# AC_Detection.net
KiCad netlist of a schematic drawn in Altium Designer
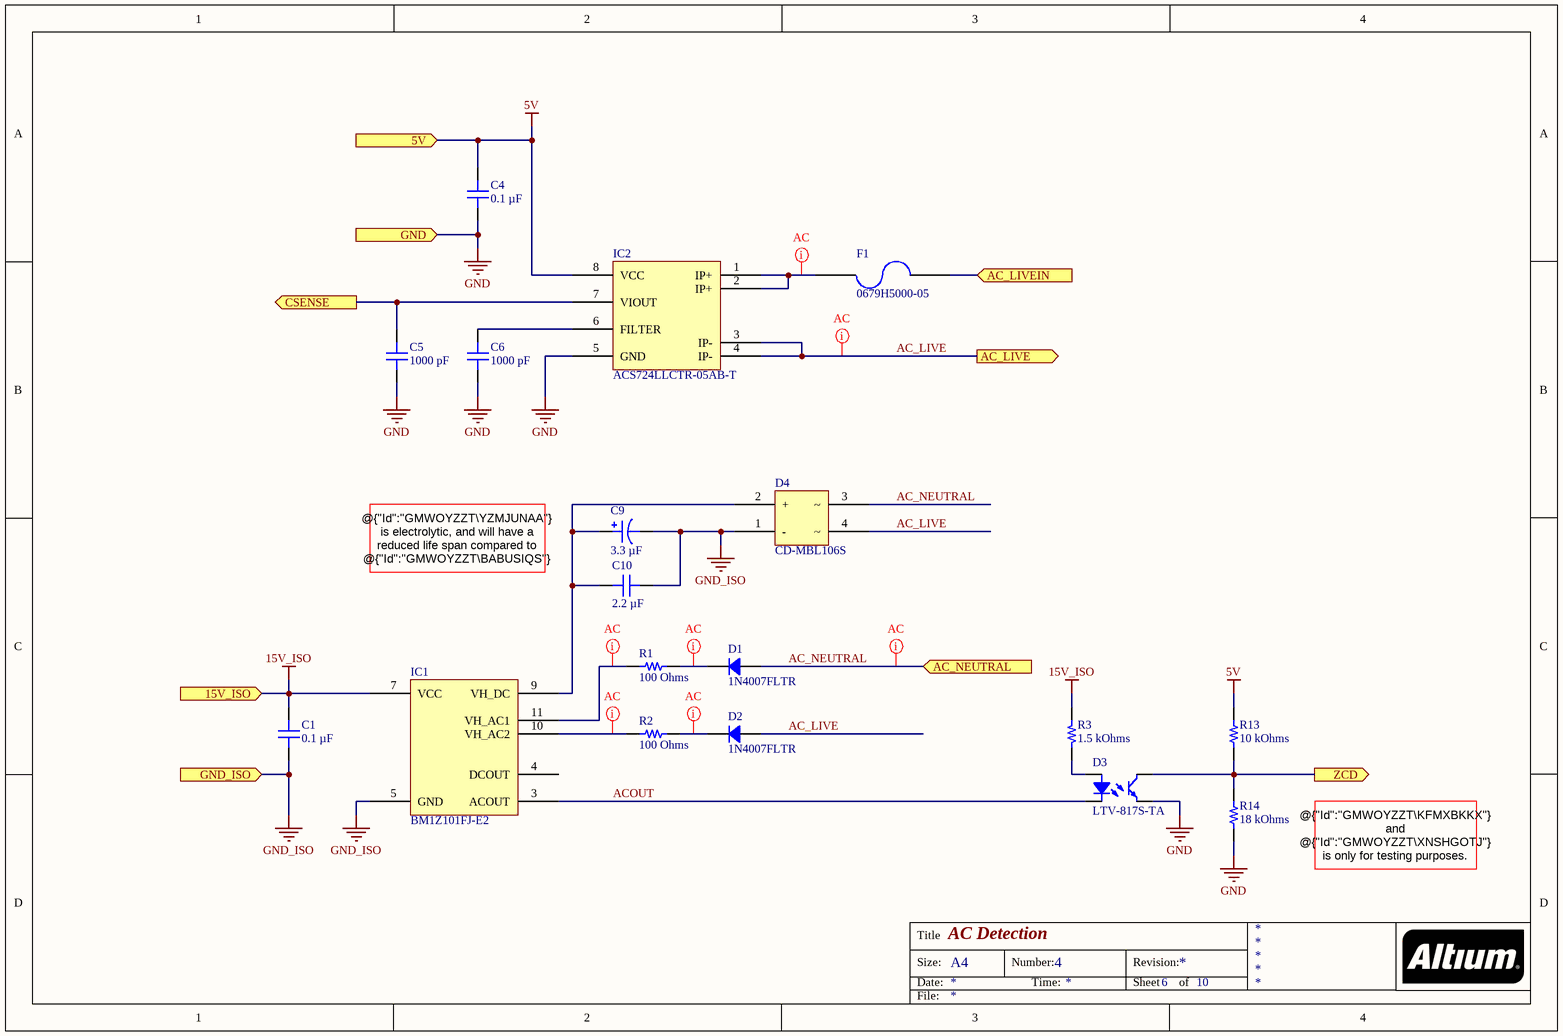
[diagram p0: AC Detection.SchDoc]

(export (version "E")
  (design (tool "Eeschema 10.0.6"))
  (components
    (comp (ref "C1")
      (value "0.1 µF")
      (footprint "CAP 0603_1608")
      (description "CAP CER 0.1UF 50V X7R 0603")
      (fields (field (name "PART NUMBER") "C0603C104K5RAC7411") (field (name "MANUFACTURER") "KEMET"))
      (libsource (lib "altiumlibrary.com") (part "Capacitor"))
    )
    (comp (ref "C4")
      (value "0.1 µF")
      (footprint "CAP 0603_1608")
      (description "CAP CER 0.1UF 50V X7R 0603")
      (fields (field (name "PART NUMBER") "C0603C104K5RAC7411") (field (name "MANUFACTURER") "KEMET"))
      (libsource (lib "altiumlibrary.com") (part "Capacitor"))
    )
    (comp (ref "C5")
      (value "1000 pF")
      (footprint "CAP 0603_1608")
      (description "CAP CER 0603 1NF 50V X7R 10%")
      (fields (field (name "PART NUMBER") "C0603X102K5RAC3316") (field (name "MANUFACTURER") "KEMET"))
      (libsource (lib "altiumlibrary.com") (part "Capacitor"))
    )
    (comp (ref "C6")
      (value "1000 pF")
      (footprint "CAP 0603_1608")
      (description "CAP CER 0603 1NF 50V X7R 10%")
      (fields (field (name "PART NUMBER") "C0603X102K5RAC3316") (field (name "MANUFACTURER") "KEMET"))
      (libsource (lib "altiumlibrary.com") (part "Capacitor"))
    )
    (comp (ref "C9")
      (value "3.3 µF")
      (footprint "CAP ALSMD ELEC 8.3MM H11MM")
      (description "CAP ALUM 3.3UF 20% 450V SMD")
      (fields (field (name "PART NUMBER") "ULV2W3R3MNL1GS") (field (name "MANUFACTURER") "Nichicon"))
      (libsource (lib "altiumlibrary.com") (part "Polarised Capacitor"))
    )
    (comp (ref "C10")
      (value "2.2 µF")
      (footprint "CAP 2220_5650 3.0MM")
      (description "CAP CER 2.2UF 450V X6S 2220")
      (fields
        (field (name "PART NUMBER") "C5750X6S2W225K250KA")
        (field (name "MANUFACTURER") "TDK Corporation")
      )
      (libsource (lib "altiumlibrary.com") (part "Capacitor"))
    )
    (comp (ref "D1")
      (value "1N4007FLTR")
      (footprint "SOD123F")
      (description "STANDARD RECTIFIER 1000V SOD-123")
      (fields (field (name "MANUFACTURER") "SMC Diode Solutions"))
      (libsource (lib "altiumlibrary.com") (part "Diode"))
    )
    (comp (ref "D2")
      (value "1N4007FLTR")
      (footprint "SOD123F")
      (description "STANDARD RECTIFIER 1000V SOD-123")
      (fields (field (name "MANUFACTURER") "SMC Diode Solutions"))
      (libsource (lib "altiumlibrary.com") (part "Diode"))
    )
    (comp (ref "D3")
      (value "LTV-817S-TA")
      (footprint "LITEON LTV-817")
      (description "OPTOISOLATR 5KV TRANSISTOR 4-SMD")
      (fields (field (name "MANUFACTURER") "Lite-On Inc."))
      (libsource (lib "altiumlibrary.com") (part "Optoisolator"))
    )
    (comp (ref "D4")
      (value "CD-MBL106S")
      (footprint "Bourns CD-MBL1xxS")
      (description "BRIDGE RECT 1PHASE 600V 1A")
      (fields (field (name "MANUFACTURER") "Bourns Inc."))
      (libsource (lib "altiumlibrary.com") (part "BOURNS CD-MBL1XXS"))
    )
    (comp (ref "F1")
      (value "0679H5000-05")
      (footprint "FUSE 2410_6125 2")
      (description "FUSE BOARD MNT 5A 350VAC 60VDC")
      (fields (field (name "MANUFACTURER") "Bel Fuse Inc."))
      (libsource (lib "altiumlibrary.com") (part "FUSE 0679H3500-05"))
    )
    (comp (ref "IC1")
      (value "BM1Z101FJ-E2")
      (footprint "ROHM SOP-J11")
      (description "IC SUPERVISOR 1 CHANNEL 11SOP")
      (fields (field (name "MANUFACTURER") "Rohm Semiconductor"))
      (libsource (lib "altiumlibrary.com") (part "ROHM BM1Z101FJ"))
    )
    (comp (ref "IC2")
      (value "ACS724LLCTR-05AB-T")
      (footprint "ALLEGRO SOICN-8 LC")
      (description "SENSOR CURRENT HALL 5A 8SOIC")
      (fields (field (name "MANUFACTURER") "Allegro MicroSystems"))
      (libsource (lib "altiumlibrary.com") (part "ALLEGRO ACS724LLC"))
    )
    (comp (ref "R1")
      (value "100 Ohms")
      (footprint "RES 1206_3216")
      (description "RES 100 OHM 5% 3/4W 1206")
      (fields (field (name "PART NUMBER") "SR1206JR-7T100RL") (field (name "MANUFACTURER") "Yageo"))
      (libsource (lib "altiumlibrary.com") (part "Resistor"))
    )
    (comp (ref "R2")
      (value "100 Ohms")
      (footprint "RES 1206_3216")
      (description "RES 100 OHM 5% 3/4W 1206")
      (fields (field (name "PART NUMBER") "SR1206JR-7T100RL") (field (name "MANUFACTURER") "Yageo"))
      (libsource (lib "altiumlibrary.com") (part "Resistor"))
    )
    (comp (ref "R3")
      (value "1.5 kOhms")
      (footprint "RES 0805_2012")
      (description "RES 1.5K OHM 1% 1/3W 0805")
      (fields
        (field (name "PART NUMBER") "CRGP0805F1K5")
        (field (name "MANUFACTURER") "TE Connectivity Passive Product")
      )
      (libsource (lib "altiumlibrary.com") (part "Resistor"))
    )
    (comp (ref "R13")
      (value "10 kOhms")
      (footprint "RES 0603_1608")
      (description "RES 10K OHM 1% 1/5W 0603")
      (fields
        (field (name "PART NUMBER") "SG73S1JTTD1002F")
        (field (name "MANUFACTURER") "KOA Speer Electronics, Inc.")
      )
      (libsource (lib "altiumlibrary.com") (part "Resistor"))
    )
    (comp (ref "R14")
      (value "18 kOhms")
      (footprint "RES 0603_1608")
      (description "RES 18K OHM 1% 1/10W 0603")
      (fields (field (name "PART NUMBER") "RC0603FR-1318KL") (field (name "MANUFACTURER") "Yageo"))
      (libsource (lib "altiumlibrary.com") (part "Resistor"))
    )
  )
  (nets
    (net (code "1") (name "/ACOUT") (class "Default")
      (node (ref "D3") (pin "2") (pinfunction "2_2") (pintype "passive"))
      (node (ref "IC1") (pin "3") (pinfunction "ACOUT_3") (pintype "passive"))
    )
    (net (code "2") (name "/AC_LIVE") (class "Default")
      (node (ref "D2") (pin "1") (pinfunction "1_1") (pintype "passive"))
      (node (ref "D4") (pin "4") (pinfunction "~_4") (pintype "passive"))
      (node (ref "IC2") (pin "3") (pinfunction "IP-_3") (pintype "passive"))
      (node (ref "IC2") (pin "4") (pinfunction "IP-_4") (pintype "passive"))
    )
    (net (code "3") (name "/AC_LIVEIN") (class "Default")
      (node (ref "F1") (pin "2") (pinfunction "2_2") (pintype "passive"))
    )
    (net (code "4") (name "/AC_NEUTRAL") (class "Default")
      (node (ref "D1") (pin "1") (pinfunction "1_1") (pintype "passive"))
      (node (ref "D4") (pin "3") (pinfunction "~_3") (pintype "passive"))
    )
    (net (code "5") (name "/CSENSE") (class "Default")
      (node (ref "C5") (pin "2") (pinfunction "2_2") (pintype "passive"))
      (node (ref "IC2") (pin "7") (pinfunction "VIOUT_7") (pintype "passive"))
    )
    (net (code "6") (name "/ZCD") (class "Default")
      (node (ref "D3") (pin "4") (pinfunction "4_4") (pintype "passive"))
      (node (ref "R13") (pin "1") (pinfunction "1_1") (pintype "passive"))
      (node (ref "R14") (pin "2") (pinfunction "2_2") (pintype "passive"))
    )
    (net (code "7") (name "5V") (class "Default")
      (node (ref "C4") (pin "2") (pinfunction "2_2") (pintype "passive"))
      (node (ref "IC2") (pin "8") (pinfunction "VCC_8") (pintype "passive"))
      (node (ref "R13") (pin "2") (pinfunction "2_2") (pintype "passive"))
    )
    (net (code "8") (name "15V_ISO") (class "Default")
      (node (ref "C1") (pin "2") (pinfunction "2_2") (pintype "passive"))
      (node (ref "IC1") (pin "7") (pinfunction "VCC_7") (pintype "passive"))
      (node (ref "R3") (pin "2") (pinfunction "2_2") (pintype "passive"))
    )
    (net (code "9") (name "GND") (class "Default")
      (node (ref "C4") (pin "1") (pinfunction "1_1") (pintype "passive"))
      (node (ref "C5") (pin "1") (pinfunction "1_1") (pintype "passive"))
      (node (ref "C6") (pin "1") (pinfunction "1_1") (pintype "passive"))
      (node (ref "D3") (pin "3") (pinfunction "3_3") (pintype "passive"))
      (node (ref "IC2") (pin "5") (pinfunction "GND_5") (pintype "passive"))
      (node (ref "R14") (pin "1") (pinfunction "1_1") (pintype "passive"))
    )
    (net (code "10") (name "GND_ISO") (class "Default")
      (node (ref "C1") (pin "1") (pinfunction "1_1") (pintype "passive"))
      (node (ref "C10") (pin "2") (pinfunction "2_2") (pintype "passive"))
      (node (ref "C9") (pin "2") (pinfunction "2_2") (pintype "passive"))
      (node (ref "D4") (pin "1") (pinfunction "-_1") (pintype "passive"))
      (node (ref "IC1") (pin "5") (pinfunction "GND_5") (pintype "passive"))
    )
    (net (code "11") (name "Net-(D1-Pad2)") (class "Default")
      (node (ref "D1") (pin "2") (pinfunction "2_2") (pintype "passive"))
      (node (ref "R1") (pin "2") (pinfunction "2_2") (pintype "passive"))
    )
    (net (code "12") (name "Net-(D2-Pad2)") (class "Default")
      (node (ref "D2") (pin "2") (pinfunction "2_2") (pintype "passive"))
      (node (ref "R2") (pin "2") (pinfunction "2_2") (pintype "passive"))
    )
    (net (code "13") (name "Net-(D3-Pad1)") (class "Default")
      (node (ref "D3") (pin "1") (pinfunction "1_1") (pintype "passive"))
      (node (ref "R3") (pin "1") (pinfunction "1_1") (pintype "passive"))
    )
    (net (code "14") (name "Net-(D4-+)") (class "Default")
      (node (ref "C10") (pin "1") (pinfunction "1_1") (pintype "passive"))
      (node (ref "C9") (pin "1") (pinfunction "1_1") (pintype "passive"))
      (node (ref "D4") (pin "2") (pinfunction "+_2") (pintype "passive"))
      (node (ref "IC1") (pin "9") (pinfunction "VH_DC_9") (pintype "passive"))
    )
    (net (code "15") (name "Net-(F1-Pad1)") (class "Default")
      (node (ref "F1") (pin "1") (pinfunction "1_1") (pintype "passive"))
      (node (ref "IC2") (pin "1") (pinfunction "IP+_1") (pintype "passive"))
      (node (ref "IC2") (pin "2") (pinfunction "IP+_2") (pintype "passive"))
    )
    (net (code "16") (name "Net-(IC1-VH_AC1)") (class "Default")
      (node (ref "IC1") (pin "11") (pinfunction "VH_AC1_11") (pintype "passive"))
      (node (ref "R1") (pin "1") (pinfunction "1_1") (pintype "passive"))
    )
    (net (code "17") (name "Net-(IC1-VH_AC2)") (class "Default")
      (node (ref "IC1") (pin "10") (pinfunction "VH_AC2_10") (pintype "passive"))
      (node (ref "R2") (pin "1") (pinfunction "1_1") (pintype "passive"))
    )
    (net (code "18") (name "Net-(IC2-FILTER)") (class "Default")
      (node (ref "C6") (pin "2") (pinfunction "2_2") (pintype "passive"))
      (node (ref "IC2") (pin "6") (pinfunction "FILTER_6") (pintype "passive"))
    )
    (net (code "19") (name "unconnected-(IC1-DCOUT-Pad4)") (class "Default")
      (node (ref "IC1") (pin "4") (pinfunction "DCOUT_4") (pintype "passive"))
    )
  )
)
